# Odroid_Headphone_Hat.net
KiCad netlist of a schematic drawn in EAGLE
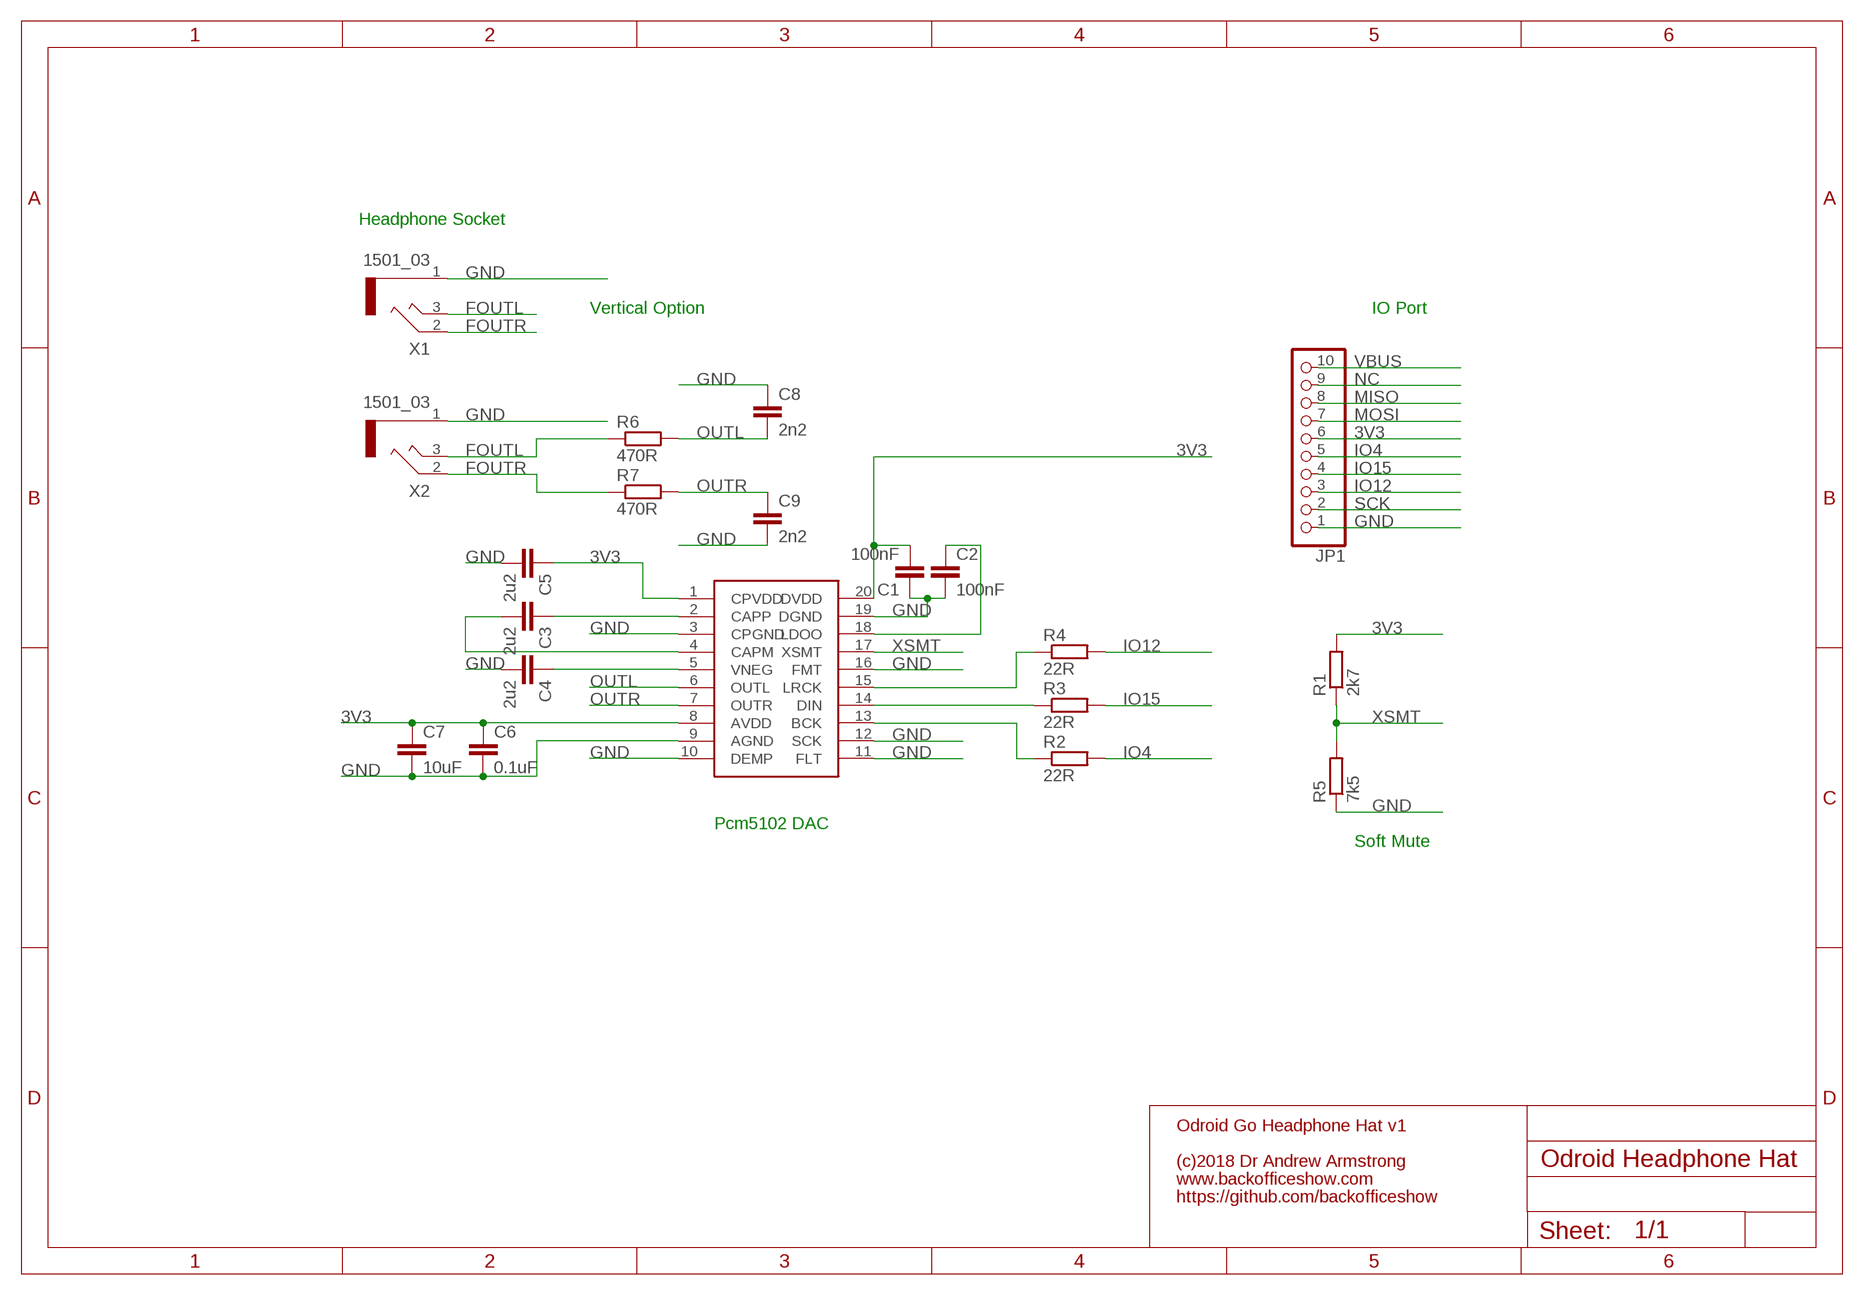
[diagram p0: schematic, sheet 1]

(export (version "E")
  (design (tool "Eeschema 10.0.6"))
  (components
    (comp (ref "C1")
      (value "100nF")
      (footprint "eagle-import:C0603")
      (libsource (lib "eagle-import") (part "C-EUC0603"))
    )
    (comp (ref "C2")
      (value "100nF")
      (footprint "eagle-import:C0603")
      (libsource (lib "eagle-import") (part "C-EUC0603"))
    )
    (comp (ref "C3")
      (value "2u2")
      (footprint "eagle-import:C0603")
      (libsource (lib "eagle-import") (part "C-EUC0603"))
    )
    (comp (ref "C4")
      (value "2u2")
      (footprint "eagle-import:C0603")
      (libsource (lib "eagle-import") (part "C-EUC0603"))
    )
    (comp (ref "C5")
      (value "2u2")
      (footprint "eagle-import:C0603")
      (libsource (lib "eagle-import") (part "C-EUC0603"))
    )
    (comp (ref "C6")
      (value "0.1uF")
      (footprint "eagle-import:C0603")
      (libsource (lib "eagle-import") (part "C-EUC0603"))
    )
    (comp (ref "C7")
      (value "10uF")
      (footprint "eagle-import:C0603")
      (libsource (lib "eagle-import") (part "C-EUC0603"))
    )
    (comp (ref "C8")
      (value "2n2")
      (footprint "eagle-import:C0603")
      (libsource (lib "eagle-import") (part "C-EUC0603"))
    )
    (comp (ref "C9")
      (value "2n2")
      (footprint "eagle-import:C0603")
      (libsource (lib "eagle-import") (part "C-EUC0603"))
    )
    (comp (ref "JP1")
      (value "PINHD-1X10/90")
      (footprint "eagle-import:1X10_90")
      (libsource (lib "eagle-import") (part "PINHD-1X10/90"))
    )
    (comp (ref "R1")
      (value "2k7")
      (footprint "eagle-import:R0603")
      (libsource (lib "eagle-import") (part "R-EU_R0603"))
    )
    (comp (ref "R2")
      (value "22R")
      (footprint "eagle-import:R0603")
      (libsource (lib "eagle-import") (part "R-EU_R0603"))
    )
    (comp (ref "R3")
      (value "22R")
      (footprint "eagle-import:R0603")
      (libsource (lib "eagle-import") (part "R-EU_R0603"))
    )
    (comp (ref "R4")
      (value "22R")
      (footprint "eagle-import:R0603")
      (libsource (lib "eagle-import") (part "R-EU_R0603"))
    )
    (comp (ref "R5")
      (value "7k5")
      (footprint "eagle-import:R0603")
      (libsource (lib "eagle-import") (part "R-EU_R0603"))
    )
    (comp (ref "R6")
      (value "470R")
      (footprint "eagle-import:R0603")
      (libsource (lib "eagle-import") (part "R-EU_R0603"))
    )
    (comp (ref "R7")
      (value "470R")
      (footprint "eagle-import:R0603")
      (libsource (lib "eagle-import") (part "R-EU_R0603"))
    )
    (comp (ref "U$1")
      (value "PCM5102")
      (footprint "eagle-import:TSSOP20")
      (libsource (lib "eagle-import") (part "PCM5102"))
    )
    (comp (ref "X1")
      (value "1501_03")
      (footprint "eagle-import:1501_03")
      (libsource (lib "eagle-import") (part "1501_03"))
    )
    (comp (ref "X2")
      (value "1501_03")
      (footprint "eagle-import:1501_03")
      (libsource (lib "eagle-import") (part "1501_03"))
    )
  )
  (nets
    (net (code "1") (name "/3V3") (class "Default")
      (node (ref "C1") (pin "2") (pinfunction "2_2") (pintype "passive"))
      (node (ref "C5") (pin "1") (pinfunction "1_1") (pintype "passive"))
      (node (ref "C6") (pin "1") (pinfunction "1_1") (pintype "passive"))
      (node (ref "C7") (pin "1") (pinfunction "1_1") (pintype "passive"))
      (node (ref "JP1") (pin "6") (pinfunction "6_6") (pintype "passive"))
      (node (ref "R1") (pin "2") (pinfunction "2_2") (pintype "passive"))
      (node (ref "U$1") (pin "1") (pinfunction "CPVDD_1") (pintype "bidirectional"))
      (node (ref "U$1") (pin "20") (pinfunction "DVDD_20") (pintype "bidirectional"))
      (node (ref "U$1") (pin "8") (pinfunction "AVDD_8") (pintype "bidirectional"))
    )
    (net (code "2") (name "/FOUTL") (class "Default")
      (node (ref "R6") (pin "1") (pinfunction "1_1") (pintype "passive"))
      (node (ref "X1") (pin "3") (pinfunction "3_3") (pintype "passive"))
      (node (ref "X2") (pin "3") (pinfunction "3_3") (pintype "passive"))
    )
    (net (code "3") (name "/FOUTR") (class "Default")
      (node (ref "R7") (pin "1") (pinfunction "1_1") (pintype "passive"))
      (node (ref "X1") (pin "2") (pinfunction "2_2") (pintype "passive"))
      (node (ref "X2") (pin "2") (pinfunction "2_2") (pintype "passive"))
    )
    (net (code "4") (name "/GND") (class "Default")
      (node (ref "C1") (pin "1") (pinfunction "1_1") (pintype "passive"))
      (node (ref "C2") (pin "2") (pinfunction "2_2") (pintype "passive"))
      (node (ref "C4") (pin "2") (pinfunction "2_2") (pintype "passive"))
      (node (ref "C5") (pin "2") (pinfunction "2_2") (pintype "passive"))
      (node (ref "C6") (pin "2") (pinfunction "2_2") (pintype "passive"))
      (node (ref "C7") (pin "2") (pinfunction "2_2") (pintype "passive"))
      (node (ref "C8") (pin "1") (pinfunction "1_1") (pintype "passive"))
      (node (ref "C9") (pin "2") (pinfunction "2_2") (pintype "passive"))
      (node (ref "JP1") (pin "1") (pinfunction "1_1") (pintype "passive"))
      (node (ref "R5") (pin "1") (pinfunction "1_1") (pintype "passive"))
      (node (ref "U$1") (pin "10") (pinfunction "DEMP_10") (pintype "bidirectional"))
      (node (ref "U$1") (pin "11") (pinfunction "FLT_11") (pintype "bidirectional"))
      (node (ref "U$1") (pin "12") (pinfunction "SCK_12") (pintype "bidirectional"))
      (node (ref "U$1") (pin "16") (pinfunction "FMT_16") (pintype "bidirectional"))
      (node (ref "U$1") (pin "19") (pinfunction "DGND_19") (pintype "bidirectional"))
      (node (ref "U$1") (pin "3") (pinfunction "CPGND_3") (pintype "bidirectional"))
      (node (ref "U$1") (pin "9") (pinfunction "AGND_9") (pintype "bidirectional"))
      (node (ref "X1") (pin "1") (pinfunction "1_1") (pintype "passive"))
      (node (ref "X2") (pin "1") (pinfunction "1_1") (pintype "passive"))
    )
    (net (code "5") (name "/IO4") (class "Default")
      (node (ref "JP1") (pin "5") (pinfunction "5_5") (pintype "passive"))
      (node (ref "R2") (pin "2") (pinfunction "2_2") (pintype "passive"))
    )
    (net (code "6") (name "/IO12") (class "Default")
      (node (ref "JP1") (pin "3") (pinfunction "3_3") (pintype "passive"))
      (node (ref "R4") (pin "2") (pinfunction "2_2") (pintype "passive"))
    )
    (net (code "7") (name "/IO15") (class "Default")
      (node (ref "JP1") (pin "4") (pinfunction "4_4") (pintype "passive"))
      (node (ref "R3") (pin "2") (pinfunction "2_2") (pintype "passive"))
    )
    (net (code "8") (name "/MISO") (class "Default")
      (node (ref "JP1") (pin "8") (pinfunction "8_8") (pintype "passive"))
    )
    (net (code "9") (name "/MOSI") (class "Default")
      (node (ref "JP1") (pin "7") (pinfunction "7_7") (pintype "passive"))
    )
    (net (code "10") (name "/NC") (class "Default")
      (node (ref "JP1") (pin "9") (pinfunction "9_9") (pintype "passive"))
    )
    (net (code "11") (name "/OUTL") (class "Default")
      (node (ref "C8") (pin "2") (pinfunction "2_2") (pintype "passive"))
      (node (ref "R6") (pin "2") (pinfunction "2_2") (pintype "passive"))
      (node (ref "U$1") (pin "6") (pinfunction "OUTL_6") (pintype "bidirectional"))
    )
    (net (code "12") (name "/OUTR") (class "Default")
      (node (ref "C9") (pin "1") (pinfunction "1_1") (pintype "passive"))
      (node (ref "R7") (pin "2") (pinfunction "2_2") (pintype "passive"))
      (node (ref "U$1") (pin "7") (pinfunction "OUTR_7") (pintype "bidirectional"))
    )
    (net (code "13") (name "/SCK") (class "Default")
      (node (ref "JP1") (pin "2") (pinfunction "2_2") (pintype "passive"))
    )
    (net (code "14") (name "/VBUS") (class "Default")
      (node (ref "JP1") (pin "10") (pinfunction "10_10") (pintype "passive"))
    )
    (net (code "15") (name "/XSMT") (class "Default")
      (node (ref "R1") (pin "1") (pinfunction "1_1") (pintype "passive"))
      (node (ref "R5") (pin "2") (pinfunction "2_2") (pintype "passive"))
      (node (ref "U$1") (pin "17") (pinfunction "XSMT_17") (pintype "bidirectional"))
    )
    (net (code "16") (name "Net-(U$1-BCK)") (class "Default")
      (node (ref "R2") (pin "1") (pinfunction "1_1") (pintype "passive"))
      (node (ref "U$1") (pin "13") (pinfunction "BCK_13") (pintype "bidirectional"))
    )
    (net (code "17") (name "Net-(U$1-CAPM)") (class "Default")
      (node (ref "C3") (pin "2") (pinfunction "2_2") (pintype "passive"))
      (node (ref "U$1") (pin "4") (pinfunction "CAPM_4") (pintype "bidirectional"))
    )
    (net (code "18") (name "Net-(U$1-CAPP)") (class "Default")
      (node (ref "C3") (pin "1") (pinfunction "1_1") (pintype "passive"))
      (node (ref "U$1") (pin "2") (pinfunction "CAPP_2") (pintype "bidirectional"))
    )
    (net (code "19") (name "Net-(U$1-DIN)") (class "Default")
      (node (ref "R3") (pin "1") (pinfunction "1_1") (pintype "passive"))
      (node (ref "U$1") (pin "14") (pinfunction "DIN_14") (pintype "bidirectional"))
    )
    (net (code "20") (name "Net-(U$1-LDOO)") (class "Default")
      (node (ref "C2") (pin "1") (pinfunction "1_1") (pintype "passive"))
      (node (ref "U$1") (pin "18") (pinfunction "LDOO_18") (pintype "bidirectional"))
    )
    (net (code "21") (name "Net-(U$1-LRCK)") (class "Default")
      (node (ref "R4") (pin "1") (pinfunction "1_1") (pintype "passive"))
      (node (ref "U$1") (pin "15") (pinfunction "LRCK_15") (pintype "bidirectional"))
    )
    (net (code "22") (name "Net-(U$1-VNEG)") (class "Default")
      (node (ref "C4") (pin "1") (pinfunction "1_1") (pintype "passive"))
      (node (ref "U$1") (pin "5") (pinfunction "VNEG_5") (pintype "bidirectional"))
    )
  )
)
